# Audio_Amplifier.net
KiCad netlist of a schematic drawn in EAGLE
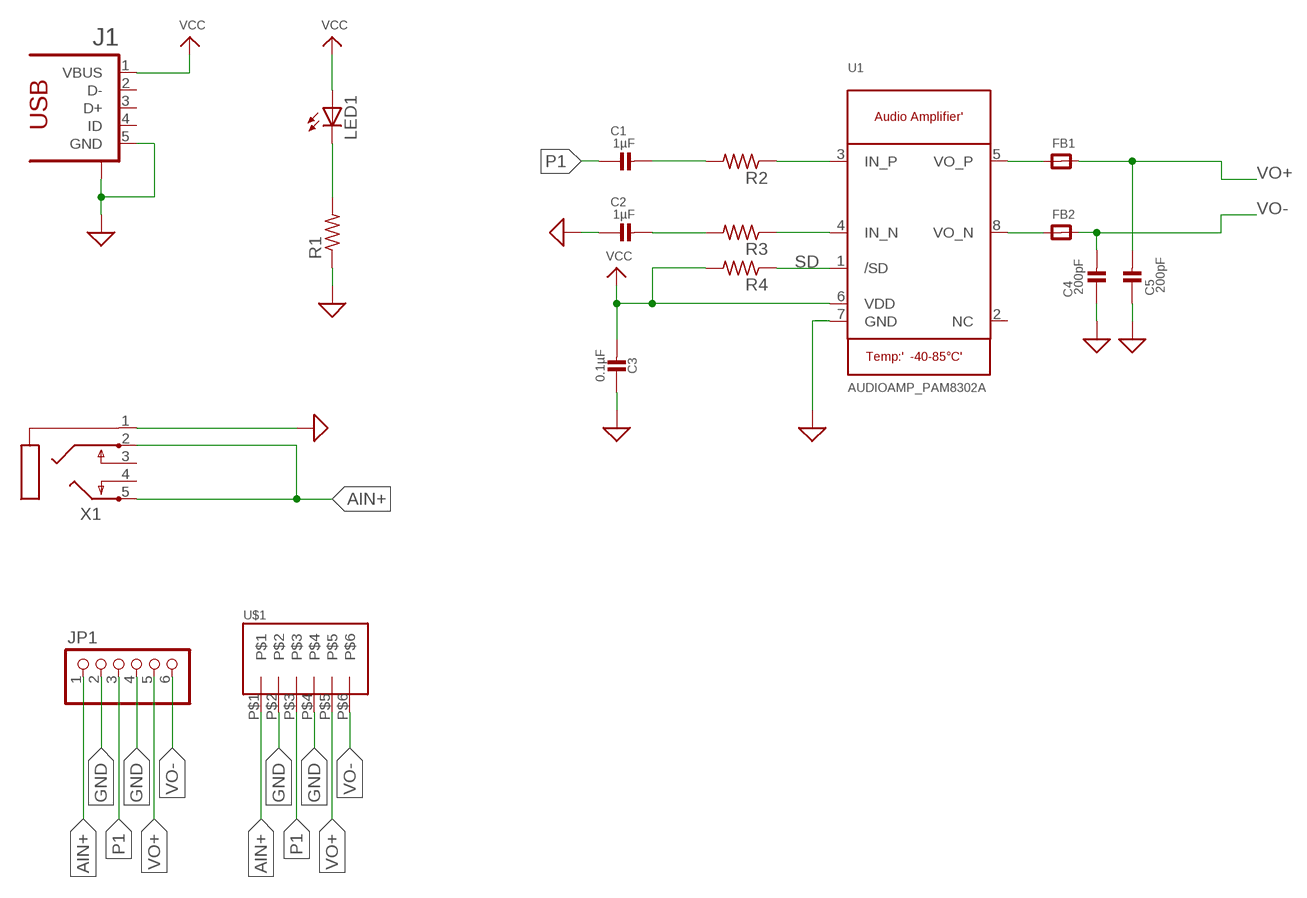
[diagram p0: schematic, sheet 1]

(export (version "E")
  (design (tool "Eeschema 10.0.6"))
  (components
    (comp (ref "C1")
      (value "1µF")
      (footprint "eagle-import:0805-NO")
      (libsource (lib "eagle-import") (part "CAP_CERAMIC0805-NOOUTLINE"))
    )
    (comp (ref "C2")
      (value "1µF")
      (footprint "eagle-import:0805-NO")
      (libsource (lib "eagle-import") (part "CAP_CERAMIC0805-NOOUTLINE"))
    )
    (comp (ref "C3")
      (value "0.1µF")
      (footprint "eagle-import:0805-NO")
      (libsource (lib "eagle-import") (part "CAP_CERAMIC0805-NOOUTLINE"))
    )
    (comp (ref "C4")
      (value "200pF")
      (footprint "eagle-import:0805-NO")
      (libsource (lib "eagle-import") (part "CAP_CERAMIC0805-NOOUTLINE"))
    )
    (comp (ref "C5")
      (value "200pF")
      (footprint "eagle-import:0805-NO")
      (libsource (lib "eagle-import") (part "CAP_CERAMIC0805-NOOUTLINE"))
    )
    (comp (ref "FB1")
      (value "FERRITE_0805")
      (footprint "eagle-import:_0805")
      (libsource (lib "eagle-import") (part "FERRITE_0805"))
    )
    (comp (ref "FB2")
      (value "FERRITE_0805")
      (footprint "eagle-import:_0805")
      (libsource (lib "eagle-import") (part "FERRITE_0805"))
    )
    (comp (ref "J1")
      (value "1981584-1")
      (footprint "eagle-import:1981584-1")
      (libsource (lib "eagle-import") (part "1981584-1"))
    )
    (comp (ref "JP1")
      (value "PINHD-1X6")
      (footprint "eagle-import:1X06")
      (libsource (lib "eagle-import") (part "PINHD-1X6"))
    )
    (comp (ref "LED1")
      (value "LEDCHIPLED_0603")
      (footprint "eagle-import:CHIPLED_0603")
      (libsource (lib "eagle-import") (part "LEDCHIPLED_0603"))
    )
    (comp (ref "R1")
      (value "330Ω")
      (footprint "eagle-import:R0603")
      (libsource (lib "eagle-import") (part "R-US_R0603"))
    )
    (comp (ref "R2")
      (value "100Ω")
      (footprint "eagle-import:R0603")
      (libsource (lib "eagle-import") (part "R-US_R0603"))
    )
    (comp (ref "R3")
      (value "100Ω")
      (footprint "eagle-import:R0603")
      (libsource (lib "eagle-import") (part "R-US_R0603"))
    )
    (comp (ref "R4")
      (value "10KΩ")
      (footprint "eagle-import:R0603")
      (libsource (lib "eagle-import") (part "R-US_R0603"))
    )
    (comp (ref "U$1")
      (value "90814-0806")
      (footprint "eagle-import:90814-0806")
      (libsource (lib "eagle-import") (part "90814-0806"))
    )
    (comp (ref "U1")
      (value "AUDIOAMP_PAM8302A")
      (footprint "eagle-import:MSOP8_0.65MM")
      (libsource (lib "eagle-import") (part "AUDIOAMP_PAM8302A"))
    )
    (comp (ref "X1")
      (value "STEREOJACK")
      (footprint "eagle-import:STX3100")
      (libsource (lib "eagle-import") (part "STEREOJACK"))
    )
  )
  (nets
    (net (code "1") (name "/SD") (class "Default")
      (node (ref "R4") (pin "1") (pinfunction "1_1") (pintype "passive"))
      (node (ref "U1") (pin "1") (pinfunction "/SD_1") (pintype "input"))
    )
    (net (code "2") (name "AIN+") (class "Default")
      (node (ref "JP1") (pin "1") (pinfunction "1_1") (pintype "passive"))
      (node (ref "U$1") (pin "P$1") (pinfunction "P$1_P$1") (pintype "bidirectional"))
      (node (ref "X1") (pin "2") (pinfunction "2_2") (pintype "passive"))
      (node (ref "X1") (pin "5") (pinfunction "5_5") (pintype "passive"))
    )
    (net (code "3") (name "GND") (class "Default")
      (node (ref "C2") (pin "1") (pinfunction "1_1") (pintype "passive"))
      (node (ref "C3") (pin "1") (pinfunction "1_1") (pintype "passive"))
      (node (ref "C4") (pin "1") (pinfunction "1_1") (pintype "passive"))
      (node (ref "C5") (pin "1") (pinfunction "1_1") (pintype "passive"))
      (node (ref "J1") (pin "5") (pinfunction "GND_5") (pintype "passive"))
      (node (ref "J1") (pin "S1") (pinfunction "S1_S1") (pintype "passive"))
      (node (ref "JP1") (pin "2") (pinfunction "2_2") (pintype "passive"))
      (node (ref "JP1") (pin "4") (pinfunction "4_4") (pintype "passive"))
      (node (ref "R1") (pin "1") (pinfunction "1_1") (pintype "passive"))
      (node (ref "U$1") (pin "P$2") (pinfunction "P$2_P$2") (pintype "bidirectional"))
      (node (ref "U$1") (pin "P$4") (pinfunction "P$4_P$4") (pintype "bidirectional"))
      (node (ref "U1") (pin "7") (pinfunction "GND_7") (pintype "power_in"))
      (node (ref "X1") (pin "1") (pinfunction "1_1") (pintype "passive"))
    )
    (net (code "4") (name "Net-(C1-Pad2)") (class "Default")
      (node (ref "C1") (pin "2") (pinfunction "2_2") (pintype "passive"))
      (node (ref "R2") (pin "2") (pinfunction "2_2") (pintype "passive"))
    )
    (net (code "5") (name "Net-(C2-Pad2)") (class "Default")
      (node (ref "C2") (pin "2") (pinfunction "2_2") (pintype "passive"))
      (node (ref "R3") (pin "2") (pinfunction "2_2") (pintype "passive"))
    )
    (net (code "6") (name "Net-(FB1-P$1)") (class "Default")
      (node (ref "FB1") (pin "1") (pinfunction "P$1_1") (pintype "passive"))
      (node (ref "U1") (pin "5") (pinfunction "VO_P_5") (pintype "output"))
    )
    (net (code "7") (name "Net-(FB2-P$1)") (class "Default")
      (node (ref "FB2") (pin "1") (pinfunction "P$1_1") (pintype "passive"))
      (node (ref "U1") (pin "8") (pinfunction "VO_N_8") (pintype "output"))
    )
    (net (code "8") (name "Net-(LED1-PadC)") (class "Default")
      (node (ref "LED1") (pin "C") (pinfunction "C_C") (pintype "passive"))
      (node (ref "R1") (pin "2") (pinfunction "2_2") (pintype "passive"))
    )
    (net (code "9") (name "Net-(U1-IN_N)") (class "Default")
      (node (ref "R3") (pin "1") (pinfunction "1_1") (pintype "passive"))
      (node (ref "U1") (pin "4") (pinfunction "IN_N_4") (pintype "input"))
    )
    (net (code "10") (name "Net-(U1-IN_P)") (class "Default")
      (node (ref "R2") (pin "1") (pinfunction "1_1") (pintype "passive"))
      (node (ref "U1") (pin "3") (pinfunction "IN_P_3") (pintype "input"))
    )
    (net (code "11") (name "P1") (class "Default")
      (node (ref "C1") (pin "1") (pinfunction "1_1") (pintype "passive"))
      (node (ref "JP1") (pin "3") (pinfunction "3_3") (pintype "passive"))
      (node (ref "U$1") (pin "P$3") (pinfunction "P$3_P$3") (pintype "bidirectional"))
    )
    (net (code "12") (name "VCC") (class "Default")
      (node (ref "C3") (pin "2") (pinfunction "2_2") (pintype "passive"))
      (node (ref "J1") (pin "1") (pinfunction "VBUS_1") (pintype "passive"))
      (node (ref "LED1") (pin "A") (pinfunction "A_A") (pintype "passive"))
      (node (ref "R4") (pin "2") (pinfunction "2_2") (pintype "passive"))
      (node (ref "U1") (pin "6") (pinfunction "VDD_6") (pintype "power_in"))
    )
    (net (code "13") (name "VO+") (class "Default")
      (node (ref "C5") (pin "2") (pinfunction "2_2") (pintype "passive"))
      (node (ref "FB1") (pin "2") (pinfunction "P$2_2") (pintype "passive"))
      (node (ref "JP1") (pin "5") (pinfunction "5_5") (pintype "passive"))
      (node (ref "U$1") (pin "P$5") (pinfunction "P$5_P$5") (pintype "bidirectional"))
    )
    (net (code "14") (name "VO-") (class "Default")
      (node (ref "C4") (pin "2") (pinfunction "2_2") (pintype "passive"))
      (node (ref "FB2") (pin "2") (pinfunction "P$2_2") (pintype "passive"))
      (node (ref "JP1") (pin "6") (pinfunction "6_6") (pintype "passive"))
      (node (ref "U$1") (pin "P$6") (pinfunction "P$6_P$6") (pintype "bidirectional"))
    )
    (net (code "15") (name "unconnected-(J1-D+-Pad3)") (class "Default")
      (node (ref "J1") (pin "3") (pinfunction "D+_3") (pintype "passive"))
    )
    (net (code "16") (name "unconnected-(J1-D--Pad2)") (class "Default")
      (node (ref "J1") (pin "2") (pinfunction "D-_2") (pintype "passive"))
    )
    (net (code "17") (name "unconnected-(J1-ID-Pad4)") (class "Default")
      (node (ref "J1") (pin "4") (pinfunction "ID_4") (pintype "passive"))
    )
    (net (code "18") (name "unconnected-(U1-NC-Pad2)") (class "Default")
      (node (ref "U1") (pin "2") (pinfunction "NC_2") (pintype "no_connect"))
    )
    (net (code "19") (name "unconnected-(X1-Pad3)") (class "Default")
      (node (ref "X1") (pin "3") (pinfunction "3_3") (pintype "passive"))
    )
    (net (code "20") (name "unconnected-(X1-Pad4)") (class "Default")
      (node (ref "X1") (pin "4") (pinfunction "4_4") (pintype "passive"))
    )
  )
)
